# PX4FMUv2_4_6_5.net
KiCad netlist of a schematic drawn in Altium Designer
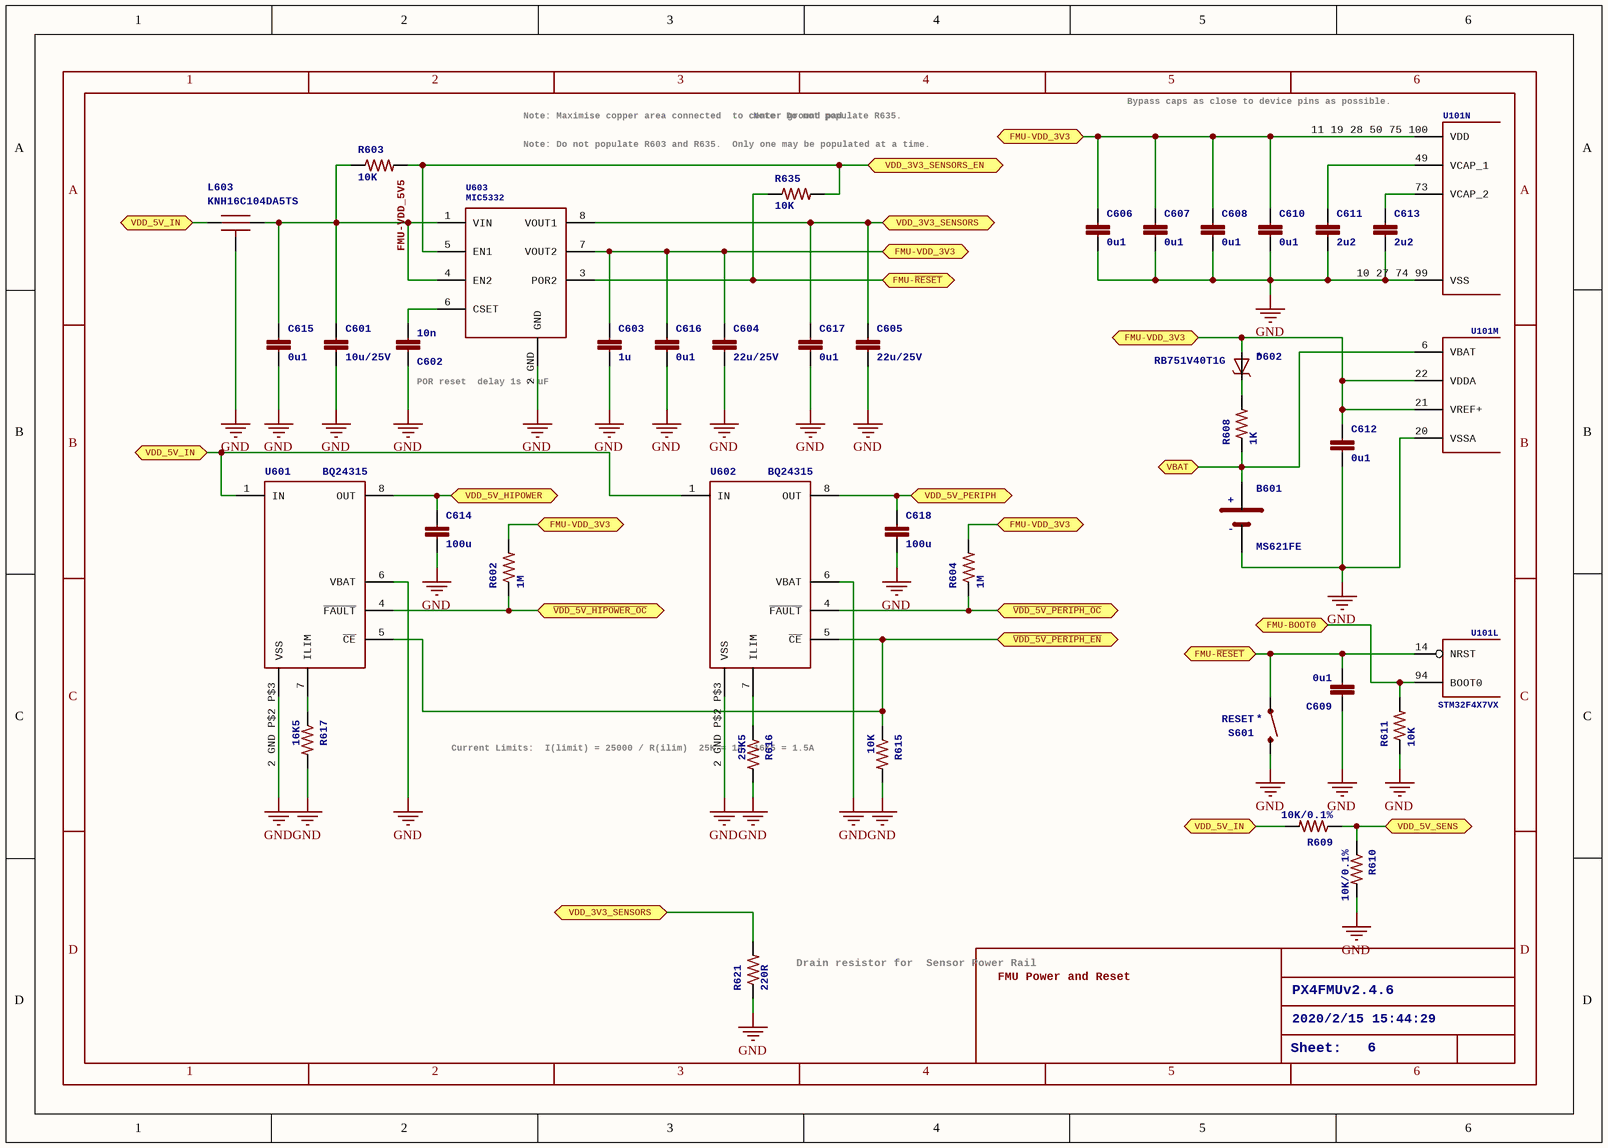
[diagram p0: PX4FMUv2.4.6_5.SchDoc]

(export (version "E")
  (design (tool "Eeschema 10.0.6"))
  (components
    (comp (ref "B601")
      (value "MS621FE")
      (footprint "MS621FE")
      (fields (field (name "PARTNO") "MS621FE-FL11E") (field (name "+") "+") (field (name "-") "-"))
      (libsource (lib "pixhawk2") (part "MS621FE"))
    )
    (comp (ref "C601")
      (value "10u/25V")
      (footprint "0805-CAP")
      (description "CapacitorStandard 0603 ceramic capacitor, and 0.1\" leaded capacitor.")
      (fields (field (name "PARTNO") "CL21A106KAYNNNE"))
      (libsource (lib "pixhawk2") (part "CAP0805"))
    )
    (comp (ref "C602")
      (value "10n")
      (footprint "0402-CAP")
      (description "CapacitorStandard 0603 ceramic capacitor, and 0.1\" leaded capacitor.")
      (fields (field (name "PARTNO") "CC0402KRX7R7BB103"))
      (libsource (lib "") (part "CAP0402_2"))
    )
    (comp (ref "C603")
      (value "1u")
      (footprint "0603-CAP")
      (description "CapacitorStandard 0603 ceramic capacitor, and 0.1\" leaded capacitor.")
      (fields (field (name "PARTNO") "CC0603ZRY5V7BB105"))
      (libsource (lib "pixhawk2") (part "CAP0603"))
    )
    (comp (ref "C604")
      (value "22u/25V")
      (footprint "0805-CAP")
      (description "CapacitorStandard 0603 ceramic capacitor, and 0.1\" leaded capacitor.")
      (fields (field (name "PARTNO") "CL21A226MAQNNNE"))
      (libsource (lib "pixhawk2") (part "CAP0805"))
    )
    (comp (ref "C605")
      (value "22u/25V")
      (footprint "0805-CAP")
      (description "CapacitorStandard 0603 ceramic capacitor, and 0.1\" leaded capacitor.")
      (fields (field (name "PARTNO") "CL21A226MAQNNNE"))
      (libsource (lib "pixhawk2") (part "CAP0805"))
    )
    (comp (ref "C606")
      (value "0u1")
      (footprint "0402-CAP")
      (description "CapacitorStandard 0603 ceramic capacitor, and 0.1\" leaded capacitor.")
      (fields (field (name "PARTNO") "CC0402ZRY5V7BB104"))
      (libsource (lib "pixhawk2") (part "CAP0402"))
    )
    (comp (ref "C607")
      (value "0u1")
      (footprint "0402-CAP")
      (description "CapacitorStandard 0603 ceramic capacitor, and 0.1\" leaded capacitor.")
      (fields (field (name "PARTNO") "CC0402ZRY5V7BB104"))
      (libsource (lib "pixhawk2") (part "CAP0402"))
    )
    (comp (ref "C608")
      (value "0u1")
      (footprint "0402-CAP")
      (description "CapacitorStandard 0603 ceramic capacitor, and 0.1\" leaded capacitor.")
      (fields (field (name "PARTNO") "CC0402ZRY5V7BB104"))
      (libsource (lib "pixhawk2") (part "CAP0402"))
    )
    (comp (ref "C609")
      (value "0u1")
      (footprint "0402-CAP")
      (description "CapacitorStandard 0603 ceramic capacitor, and 0.1\" leaded capacitor.")
      (fields (field (name "PARTNO") "CC0402ZRY5V7BB104"))
      (libsource (lib "") (part "CAP0402_1"))
    )
    (comp (ref "C610")
      (value "0u1")
      (footprint "0402-CAP")
      (description "CapacitorStandard 0603 ceramic capacitor, and 0.1\" leaded capacitor.")
      (fields (field (name "PARTNO") "CC0402ZRY5V7BB104"))
      (libsource (lib "pixhawk2") (part "CAP0402"))
    )
    (comp (ref "C611")
      (value "2u2")
      (footprint "0603-CAP")
      (description "CapacitorStandard 0603 ceramic capacitor, and 0.1\" leaded capacitor.")
      (fields (field (name "PARTNO") "C1608X6S1C225K080AC"))
      (libsource (lib "pixhawk2") (part "CAP0603"))
    )
    (comp (ref "C612")
      (value "0u1")
      (footprint "0402-CAP")
      (description "CapacitorStandard 0603 ceramic capacitor, and 0.1\" leaded capacitor.")
      (fields (field (name "PARTNO") "CC0402ZRY5V7BB104"))
      (libsource (lib "pixhawk2") (part "CAP0402"))
    )
    (comp (ref "C613")
      (value "2u2")
      (footprint "0603-CAP")
      (description "CapacitorStandard 0603 ceramic capacitor, and 0.1\" leaded capacitor.")
      (fields (field (name "PARTNO") "C1608X6S1C225K080AC"))
      (libsource (lib "pixhawk2") (part "CAP0603"))
    )
    (comp (ref "C614")
      (value "100u")
      (footprint "1206-CAP")
      (description "CapacitorStandard 0603 ceramic capacitor, and 0.1\" leaded capacitor.")
      (fields (field (name "PARTNO") "C3216X5R1A107M160AC"))
      (libsource (lib "pixhawk2") (part "CAP1206"))
    )
    (comp (ref "C615")
      (value "0u1")
      (footprint "0402-CAP")
      (description "CapacitorStandard 0603 ceramic capacitor, and 0.1\" leaded capacitor.")
      (fields (field (name "PARTNO") "CC0402ZRY5V7BB104"))
      (libsource (lib "pixhawk2") (part "CAP0402"))
    )
    (comp (ref "C616")
      (value "0u1")
      (footprint "0402-CAP")
      (description "CapacitorStandard 0603 ceramic capacitor, and 0.1\" leaded capacitor.")
      (fields (field (name "PARTNO") "CC0402ZRY5V7BB104"))
      (libsource (lib "pixhawk2") (part "CAP0402"))
    )
    (comp (ref "C617")
      (value "0u1")
      (footprint "0402-CAP")
      (description "CapacitorStandard 0603 ceramic capacitor, and 0.1\" leaded capacitor.")
      (fields (field (name "PARTNO") "CC0402ZRY5V7BB104"))
      (libsource (lib "pixhawk2") (part "CAP0402"))
    )
    (comp (ref "C618")
      (value "100u")
      (footprint "1206-CAP")
      (description "CapacitorStandard 0603 ceramic capacitor, and 0.1\" leaded capacitor.")
      (fields (field (name "PARTNO") "C3216X5R1A107M160AC"))
      (libsource (lib "pixhawk2") (part "CAP1206"))
    )
    (comp (ref "D602")
      (value "RB751V40T1G")
      (footprint "SOD323")
      (description "Schottky barrier diode in DO214AC, e.g. Fairchild SS14.")
      (fields (field (name "NAME") "*"))
      (libsource (lib "pixhawk2") (part "DIODE-SCHOTTKY_SOD323"))
    )
    (comp (ref "L603")
      (value "KNH16C104DA5TS")
      (footprint "KYOCERA-KNH16-DA")
      (description "Kyocera KNH16C104DA5TS EMI filter")
      (libsource (lib "pixhawk2") (part "KNH16C104DA5TS"))
    )
    (comp (ref "R602")
      (value "1M")
      (footprint "0402-RES")
      (fields (field (name "PARTNO") "RC0402FR-071ML"))
      (libsource (lib "pixhawk2") (part "RESISTOR0402-RES"))
    )
    (comp (ref "R603")
      (value "10K")
      (footprint "0402-RES")
      (fields (field (name "PARTNO") "RC0402FR-0710KL"))
      (libsource (lib "pixhawk2") (part "RESISTOR0402-RES"))
    )
    (comp (ref "R604")
      (value "1M")
      (footprint "0402-RES")
      (fields (field (name "PARTNO") "RC0402FR-071ML"))
      (libsource (lib "pixhawk2") (part "RESISTOR0402-RES"))
    )
    (comp (ref "R608")
      (value "1K")
      (footprint "0402-RES")
      (fields (field (name "PARTNO") "RC0402FR-071KL"))
      (libsource (lib "pixhawk2") (part "RESISTOR0402-RES"))
    )
    (comp (ref "R609")
      (value "10K/0.1%")
      (footprint "0402-RES")
      (fields (field (name "PARTNO") "ERA-2AEB103X"))
      (libsource (lib "pixhawk2") (part "RESISTOR0402-RES"))
    )
    (comp (ref "R610")
      (value "10K/0.1%")
      (footprint "0402-RES")
      (fields (field (name "PARTNO") "ERA-2AEB103X"))
      (libsource (lib "pixhawk2") (part "RESISTOR0402-RES"))
    )
    (comp (ref "R611")
      (value "10K")
      (footprint "0402-RES")
      (fields (field (name "PARTNO") "RC0402FR-0710KL"))
      (libsource (lib "pixhawk2") (part "RESISTOR0402-RES"))
    )
    (comp (ref "R615")
      (value "10K")
      (footprint "0402-RES")
      (fields (field (name "PARTNO") "RC0402FR-0710KL"))
      (libsource (lib "pixhawk2") (part "RESISTOR0402-RES"))
    )
    (comp (ref "R616")
      (value "25K5")
      (footprint "0402-RES")
      (fields (field (name "PARTNO") "RMCF0402FT25K5"))
      (libsource (lib "pixhawk2") (part "RESISTOR0402-RES"))
    )
    (comp (ref "R617")
      (value "16K5")
      (footprint "0402-RES")
      (fields (field (name "PARTNO") "RMCF0402FT16K5"))
      (libsource (lib "pixhawk2") (part "RESISTOR0402-RES"))
    )
    (comp (ref "R621")
      (value "220R")
      (footprint "0603-RES")
      (fields (field (name "PARTNO") "RC1608J100CS"))
      (libsource (lib "pixhawk2") (part "RESISTOR0603-RES"))
    )
    (comp (ref "R635")
      (value "10K")
      (footprint "0402-RES")
      (fields (field (name "PARTNO") "RC0402FR-0710KL"))
      (libsource (lib "pixhawk2") (part "RESISTOR0402-RES"))
    )
    (comp (ref "S601")
      (value "RESET")
      (footprint "EVQP7J01K")
      (fields (field (name "NAME") "*") (field (name "PARTNO") "EVQ-P7J01P"))
      (libsource (lib "pixhawk2") (part "SWITCH-MOMENTARY-2"))
    )
    (comp (ref "U101")
      (value "STM32F4X7VX")
      (footprint "TQFP100")
      (fields (field (name "PARTNO") "STM32F427VI"))
      (libsource (lib "pixhawk2") (part "STM32F4X7VX"))
    )
    (comp (ref "U601")
      (value "BQ24315")
      (footprint "QFN8-DSG")
      (fields (field (name "PARTNO") "BQ24315DSGR"))
      (libsource (lib "pixhawk2") (part "BQ24315"))
    )
    (comp (ref "U602")
      (value "BQ24315")
      (footprint "QFN8-DSG")
      (fields (field (name "PARTNO") "BQ24315DSGR"))
      (libsource (lib "pixhawk2") (part "BQ24315"))
    )
    (comp (ref "U603")
      (value "MIC5332")
      (footprint "MLF-8-EPAD")
      (fields (field (name "PARTNO") "MIC5332-SSYMT"))
      (libsource (lib "pixhawk2") (part "MIC5332"))
    )
  )
  (nets
    (net (code "1") (name "/FMU-BOOT0") (class "Default")
      (node (ref "R611") (pin "P$2") (pinfunction "2_P$2") (pintype "passive"))
      (node (ref "U101") (pin "94") (pinfunction "BOOT0_94") (pintype "passive"))
    )
    (net (code "2") (name "/FMU-VDD_3V3") (class "Default")
      (node (ref "C603") (pin "P$1") (pinfunction "1_P$1") (pintype "passive"))
      (node (ref "C604") (pin "P$1") (pinfunction "1_P$1") (pintype "passive"))
      (node (ref "C606") (pin "P$1") (pinfunction "1_P$1") (pintype "passive"))
      (node (ref "C607") (pin "P$1") (pinfunction "1_P$1") (pintype "passive"))
      (node (ref "C608") (pin "P$1") (pinfunction "1_P$1") (pintype "passive"))
      (node (ref "C610") (pin "P$1") (pinfunction "1_P$1") (pintype "passive"))
      (node (ref "C612") (pin "P$1") (pinfunction "1_P$1") (pintype "passive"))
      (node (ref "C616") (pin "P$1") (pinfunction "1_P$1") (pintype "passive"))
      (node (ref "D602") (pin "A") (pinfunction "A_A") (pintype "passive"))
      (node (ref "R602") (pin "P$2") (pinfunction "2_P$2") (pintype "passive"))
      (node (ref "R604") (pin "P$2") (pinfunction "2_P$2") (pintype "passive"))
      (node (ref "U101") (pin "11_19_28_50_75_100") (pinfunction "VDD_11_19_28_50_75_100") (pintype "power_in"))
      (node (ref "U101") (pin "21") (pinfunction "VREF+_21") (pintype "passive"))
      (node (ref "U101") (pin "22") (pinfunction "VDDA_22") (pintype "power_in"))
      (node (ref "U603") (pin "7") (pinfunction "VOUT2_7") (pintype "passive"))
    )
    (net (code "3") (name "/FMU-VDD_5V5") (class "Default")
      (node (ref "C601") (pin "P$1") (pinfunction "1_P$1") (pintype "passive"))
      (node (ref "C615") (pin "P$1") (pinfunction "1_P$1") (pintype "passive"))
      (node (ref "L603") (pin "P$2") (pinfunction "P$2_P$2") (pintype "passive"))
      (node (ref "R603") (pin "P$1") (pinfunction "1_P$1") (pintype "passive"))
      (node (ref "U603") (pin "1") (pinfunction "VIN_1") (pintype "passive"))
      (node (ref "U603") (pin "4") (pinfunction "EN2_4") (pintype "passive"))
    )
    (net (code "4") (name "/FMU-~{RESET}") (class "Default")
      (node (ref "C609") (pin "P$2") (pinfunction "2_P$2") (pintype "passive"))
      (node (ref "R635") (pin "P$1") (pinfunction "1_P$1") (pintype "passive"))
      (node (ref "S601") (pin "A1") (pinfunction "1_A1") (pintype "passive"))
      (node (ref "U101") (pin "14") (pinfunction "NRST_14") (pintype "passive"))
      (node (ref "U603") (pin "3") (pinfunction "POR2_3") (pintype "passive"))
    )
    (net (code "5") (name "/VBAT") (class "Default")
      (node (ref "B601") (pin "1") (pinfunction "POS_1") (pintype "passive"))
      (node (ref "R608") (pin "P$1") (pinfunction "1_P$1") (pintype "passive"))
      (node (ref "U101") (pin "6") (pinfunction "VBAT_6") (pintype "power_in"))
    )
    (net (code "6") (name "/VDD_3V3_SENSORS") (class "Default")
      (node (ref "C605") (pin "P$1") (pinfunction "1_P$1") (pintype "passive"))
      (node (ref "C617") (pin "P$1") (pinfunction "1_P$1") (pintype "passive"))
      (node (ref "R621") (pin "2") (pinfunction "2_2") (pintype "passive"))
      (node (ref "U603") (pin "8") (pinfunction "VOUT1_8") (pintype "passive"))
    )
    (net (code "7") (name "/VDD_3V3_SENSORS_EN") (class "Default")
      (node (ref "R603") (pin "P$2") (pinfunction "2_P$2") (pintype "passive"))
      (node (ref "R635") (pin "P$2") (pinfunction "2_P$2") (pintype "passive"))
      (node (ref "U603") (pin "5") (pinfunction "EN1_5") (pintype "passive"))
    )
    (net (code "8") (name "/VDD_5V_HIPOWER") (class "Default")
      (node (ref "C614") (pin "P$1") (pinfunction "1_P$1") (pintype "passive"))
      (node (ref "U601") (pin "8") (pinfunction "OUT_8") (pintype "passive"))
    )
    (net (code "9") (name "/VDD_5V_IN") (class "Default")
      (node (ref "L603") (pin "P$1") (pinfunction "P$1_P$1") (pintype "passive"))
      (node (ref "R609") (pin "P$2") (pinfunction "2_P$2") (pintype "passive"))
      (node (ref "U601") (pin "1") (pinfunction "IN_1") (pintype "passive"))
      (node (ref "U602") (pin "1") (pinfunction "IN_1") (pintype "passive"))
    )
    (net (code "10") (name "/VDD_5V_PERIPH") (class "Default")
      (node (ref "C618") (pin "P$1") (pinfunction "1_P$1") (pintype "passive"))
      (node (ref "U602") (pin "8") (pinfunction "OUT_8") (pintype "passive"))
    )
    (net (code "11") (name "/VDD_5V_SENS") (class "Default")
      (node (ref "R609") (pin "P$1") (pinfunction "1_P$1") (pintype "passive"))
      (node (ref "R610") (pin "P$1") (pinfunction "1_P$1") (pintype "passive"))
    )
    (net (code "12") (name "/~{VDD_5V_HIPOWER_OC}") (class "Default")
      (node (ref "R602") (pin "P$1") (pinfunction "1_P$1") (pintype "passive"))
      (node (ref "U601") (pin "4") (pinfunction "~{FAULT}_4") (pintype "passive"))
    )
    (net (code "13") (name "/~{VDD_5V_PERIPH_EN}") (class "Default")
      (node (ref "R615") (pin "P$1") (pinfunction "1_P$1") (pintype "passive"))
      (node (ref "U601") (pin "5") (pinfunction "~{CE}_5") (pintype "passive"))
      (node (ref "U602") (pin "5") (pinfunction "~{CE}_5") (pintype "passive"))
    )
    (net (code "14") (name "/~{VDD_5V_PERIPH_OC}") (class "Default")
      (node (ref "R604") (pin "P$1") (pinfunction "1_P$1") (pintype "passive"))
      (node (ref "U602") (pin "4") (pinfunction "~{FAULT}_4") (pintype "passive"))
    )
    (net (code "15") (name "GND") (class "Default")
      (node (ref "B601") (pin "2") (pinfunction "NEG_2") (pintype "passive"))
      (node (ref "C601") (pin "P$2") (pinfunction "2_P$2") (pintype "passive"))
      (node (ref "C602") (pin "P$1") (pinfunction "1_P$1") (pintype "passive"))
      (node (ref "C603") (pin "P$2") (pinfunction "2_P$2") (pintype "passive"))
      (node (ref "C604") (pin "P$2") (pinfunction "2_P$2") (pintype "passive"))
      (node (ref "C605") (pin "P$2") (pinfunction "2_P$2") (pintype "passive"))
      (node (ref "C606") (pin "P$2") (pinfunction "2_P$2") (pintype "passive"))
      (node (ref "C607") (pin "P$2") (pinfunction "2_P$2") (pintype "passive"))
      (node (ref "C608") (pin "P$2") (pinfunction "2_P$2") (pintype "passive"))
      (node (ref "C609") (pin "P$1") (pinfunction "1_P$1") (pintype "passive"))
      (node (ref "C610") (pin "P$2") (pinfunction "2_P$2") (pintype "passive"))
      (node (ref "C611") (pin "P$2") (pinfunction "2_P$2") (pintype "passive"))
      (node (ref "C612") (pin "P$2") (pinfunction "2_P$2") (pintype "passive"))
      (node (ref "C613") (pin "P$2") (pinfunction "2_P$2") (pintype "passive"))
      (node (ref "C614") (pin "P$2") (pinfunction "2_P$2") (pintype "passive"))
      (node (ref "C615") (pin "P$2") (pinfunction "2_P$2") (pintype "passive"))
      (node (ref "C616") (pin "P$2") (pinfunction "2_P$2") (pintype "passive"))
      (node (ref "C617") (pin "P$2") (pinfunction "2_P$2") (pintype "passive"))
      (node (ref "C618") (pin "P$2") (pinfunction "2_P$2") (pintype "passive"))
      (node (ref "L603") (pin "P$3_P$4_P$5") (pinfunction "P$3_P$3_P$4_P$5") (pintype "passive"))
      (node (ref "R610") (pin "P$2") (pinfunction "2_P$2") (pintype "passive"))
      (node (ref "R611") (pin "P$1") (pinfunction "1_P$1") (pintype "passive"))
      (node (ref "R615") (pin "P$2") (pinfunction "2_P$2") (pintype "passive"))
      (node (ref "R616") (pin "P$2") (pinfunction "2_P$2") (pintype "passive"))
      (node (ref "R617") (pin "P$2") (pinfunction "2_P$2") (pintype "passive"))
      (node (ref "R621") (pin "1") (pinfunction "1_1") (pintype "passive"))
      (node (ref "S601") (pin "B3") (pinfunction "2_B3") (pintype "passive"))
      (node (ref "U101") (pin "10_27_74_99") (pinfunction "VSS_10_27_74_99") (pintype "power_in"))
      (node (ref "U101") (pin "20") (pinfunction "VSSA_20") (pintype "power_in"))
      (node (ref "U601") (pin "2_GND_P$2_P$3") (pinfunction "VSS_2_GND_P$2_P$3") (pintype "passive"))
      (node (ref "U601") (pin "6") (pinfunction "VBAT_6") (pintype "passive"))
      (node (ref "U602") (pin "2_GND_P$2_P$3") (pinfunction "VSS_2_GND_P$2_P$3") (pintype "passive"))
      (node (ref "U602") (pin "6") (pinfunction "VBAT_6") (pintype "passive"))
      (node (ref "U603") (pin "2_GND") (pinfunction "GND_2_GND") (pintype "passive"))
    )
    (net (code "16") (name "Net-(C602-2)") (class "Default")
      (node (ref "C602") (pin "P$2") (pinfunction "2_P$2") (pintype "passive"))
      (node (ref "U603") (pin "6") (pinfunction "CSET_6") (pintype "passive"))
    )
    (net (code "17") (name "Net-(C611-1)") (class "Default")
      (node (ref "C611") (pin "P$1") (pinfunction "1_P$1") (pintype "passive"))
      (node (ref "U101") (pin "49") (pinfunction "VCAP_1_49") (pintype "power_in"))
    )
    (net (code "18") (name "Net-(C613-1)") (class "Default")
      (node (ref "C613") (pin "P$1") (pinfunction "1_P$1") (pintype "passive"))
      (node (ref "U101") (pin "73") (pinfunction "VCAP_2_73") (pintype "power_in"))
    )
    (net (code "19") (name "Net-(R608-2)") (class "Default")
      (node (ref "D602") (pin "C") (pinfunction "C_C") (pintype "passive"))
      (node (ref "R608") (pin "P$2") (pinfunction "2_P$2") (pintype "passive"))
    )
    (net (code "20") (name "Net-(R616-1)") (class "Default")
      (node (ref "R616") (pin "P$1") (pinfunction "1_P$1") (pintype "passive"))
      (node (ref "U602") (pin "7") (pinfunction "ILIM_7") (pintype "passive"))
    )
    (net (code "21") (name "Net-(R617-1)") (class "Default")
      (node (ref "R617") (pin "P$1") (pinfunction "1_P$1") (pintype "passive"))
      (node (ref "U601") (pin "7") (pinfunction "ILIM_7") (pintype "passive"))
    )
  )
)
